# Bluetooth.net
KiCad netlist of a schematic drawn in EAGLE
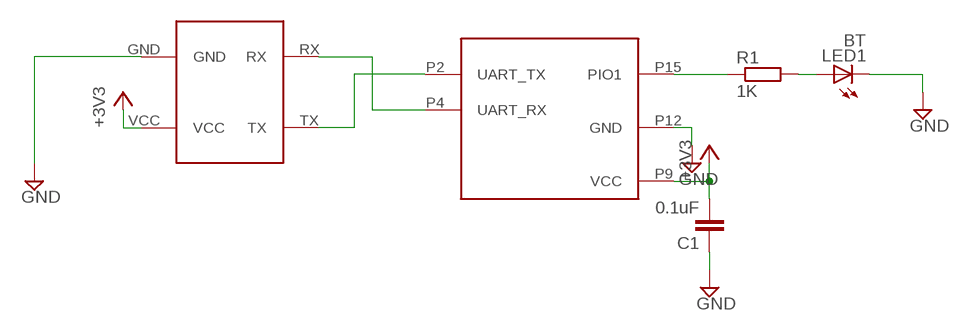
[diagram p0: schematic, sheet 1]

(export (version "E")
  (design (tool "Eeschema 10.0.6"))
  (components
    (comp (ref "C1")
      (value "0.1uF")
      (footprint "eagle-import:C0805")
      (libsource (lib "eagle-import") (part "C-EUC0805"))
    )
    (comp (ref "LED1")
      (value "BT")
      (footprint "eagle-import:CHIPLED_0805")
      (libsource (lib "eagle-import") (part "LEDCHIPLED_0805"))
    )
    (comp (ref "R1")
      (value "1K")
      (footprint "eagle-import:R0805")
      (libsource (lib "eagle-import") (part "R-EU_R0805"))
    )
    (comp (ref "U$1")
      (value "BLUESIMPLE")
      (footprint "eagle-import:BLUESIMPLE")
      (libsource (lib "eagle-import") (part "BLUESIMPLE"))
    )
    (comp (ref "U$2")
      (value "BLUE-BOARD")
      (footprint "eagle-import:BLUE-BOARD")
      (libsource (lib "eagle-import") (part "BLUE-BOARD"))
    )
  )
  (nets
    (net (code "1") (name "+3V3") (class "Default")
      (node (ref "C1") (pin "2") (pinfunction "2_2") (pintype "passive"))
      (node (ref "U$1") (pin "P9") (pinfunction "VCC_P9") (pintype "bidirectional"))
      (node (ref "U$2") (pin "VCC") (pinfunction "VCC_VCC") (pintype "bidirectional"))
    )
    (net (code "2") (name "GND") (class "Default")
      (node (ref "C1") (pin "1") (pinfunction "1_1") (pintype "passive"))
      (node (ref "LED1") (pin "C") (pinfunction "C_C") (pintype "passive"))
      (node (ref "U$1") (pin "P12") (pinfunction "GND_P12") (pintype "bidirectional"))
      (node (ref "U$2") (pin "GND") (pinfunction "GND_GND") (pintype "bidirectional"))
    )
    (net (code "3") (name "Net-(LED1-PadA)") (class "Default")
      (node (ref "LED1") (pin "A") (pinfunction "A_A") (pintype "passive"))
      (node (ref "R1") (pin "2") (pinfunction "2_2") (pintype "passive"))
    )
    (net (code "4") (name "Net-(U$1-PIO1)") (class "Default")
      (node (ref "R1") (pin "1") (pinfunction "1_1") (pintype "passive"))
      (node (ref "U$1") (pin "P15") (pinfunction "PIO1_P15") (pintype "bidirectional"))
    )
    (net (code "5") (name "Net-(U$1-UART_RX)") (class "Default")
      (node (ref "U$1") (pin "P4") (pinfunction "UART_RX_P4") (pintype "bidirectional"))
      (node (ref "U$2") (pin "RX") (pinfunction "RX_RX") (pintype "bidirectional"))
    )
    (net (code "6") (name "Net-(U$1-UART_TX)") (class "Default")
      (node (ref "U$1") (pin "P2") (pinfunction "UART_TX_P2") (pintype "bidirectional"))
      (node (ref "U$2") (pin "TX") (pinfunction "TX_TX") (pintype "bidirectional"))
    )
  )
)
